# IOIO_Pump_Unrouted.net
KiCad netlist of a schematic drawn in EAGLE
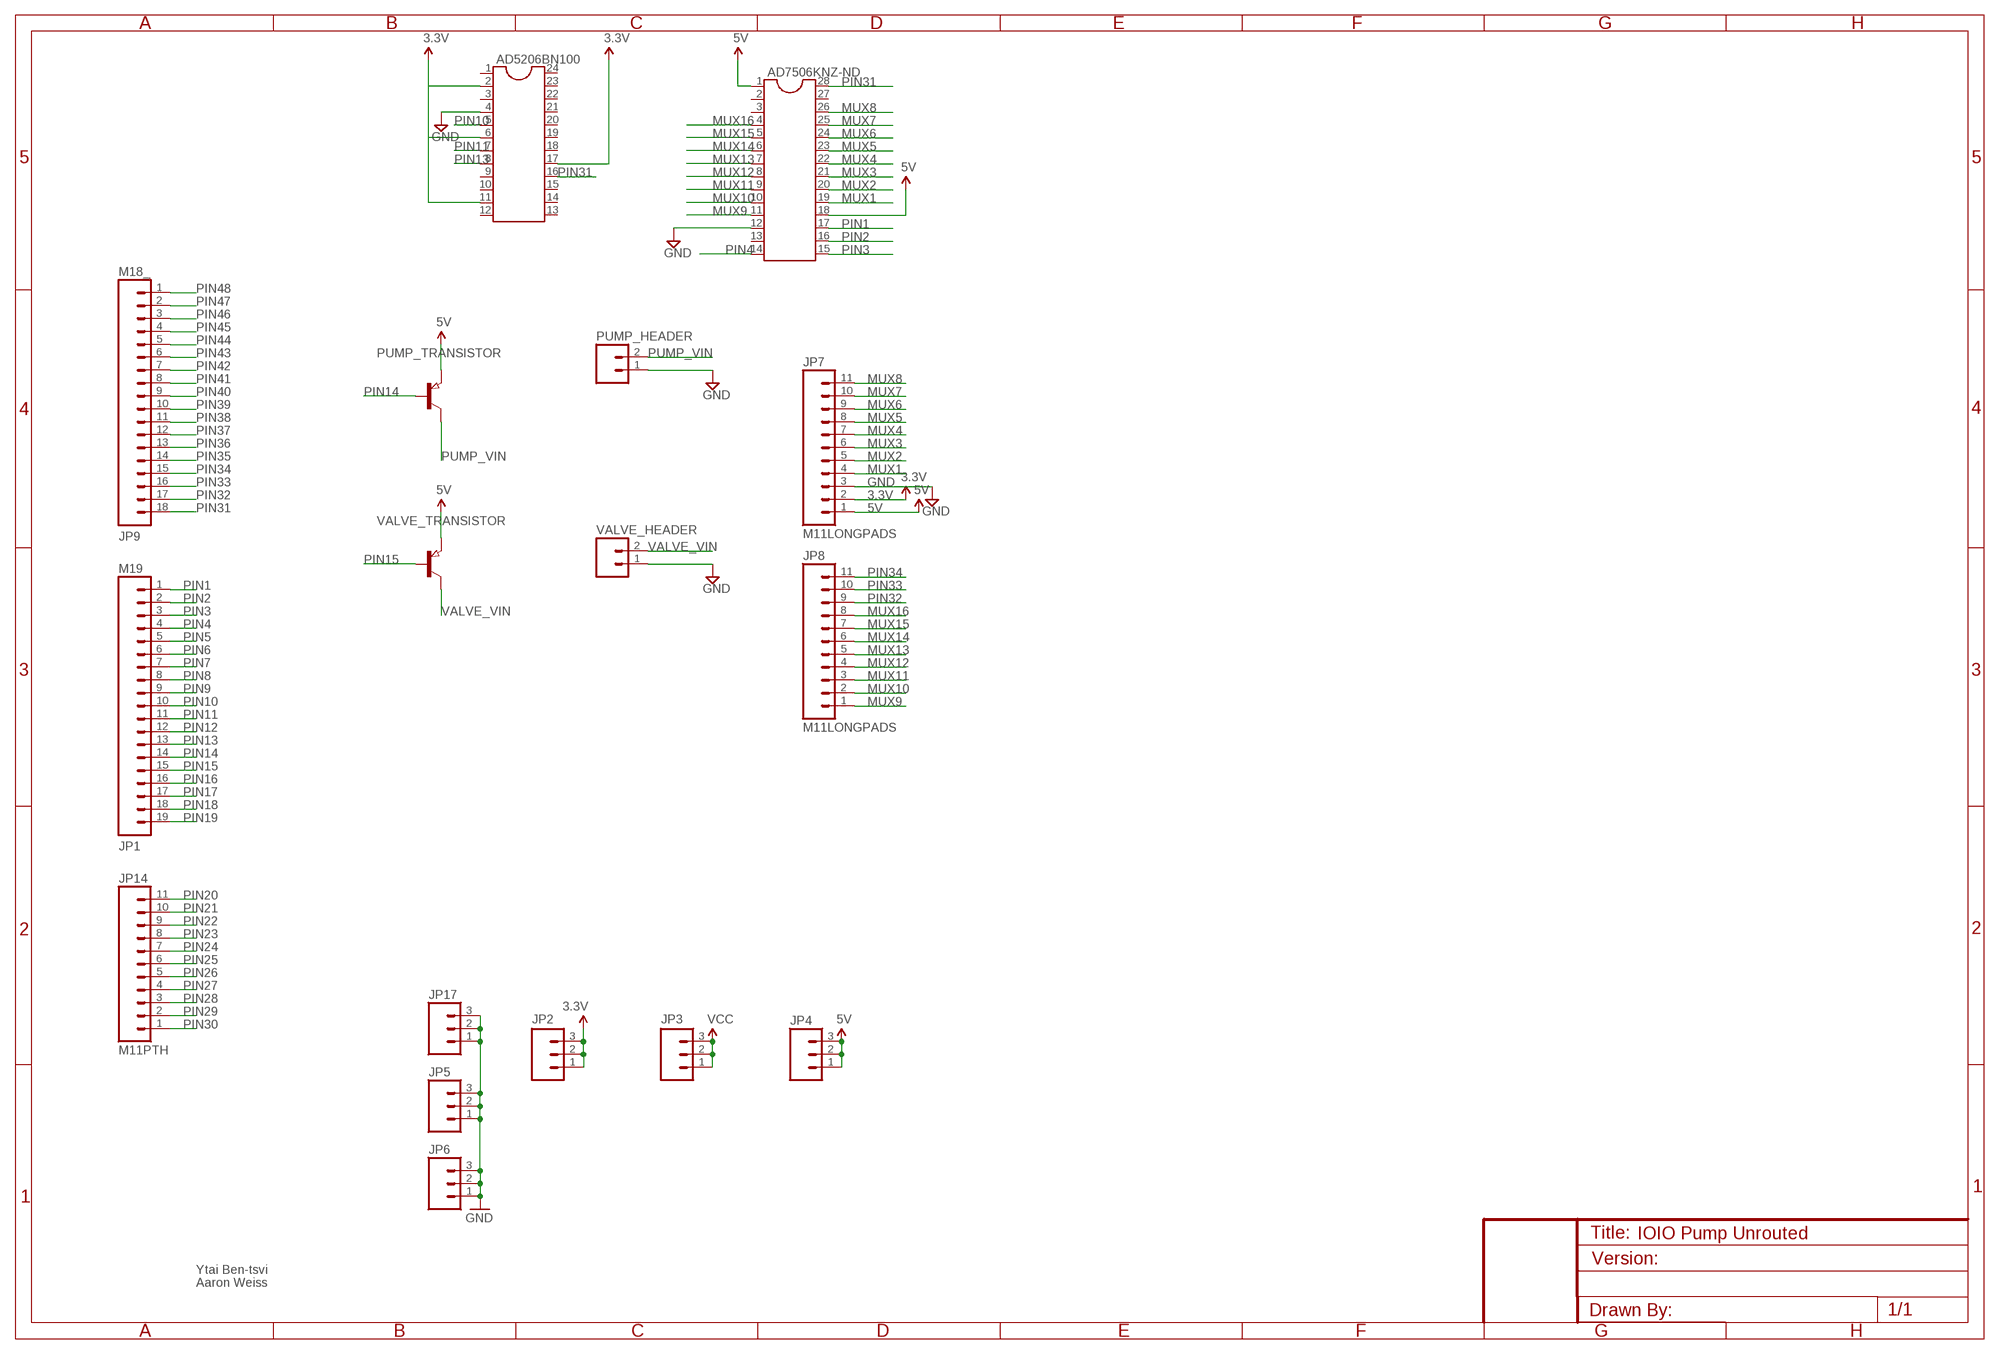
[diagram p0: schematic, sheet 1]

(export (version "E")
  (design (tool "Eeschema 10.0.6"))
  (components
    (comp (ref "AD5206BN100")
      (value "DIL24-3")
      (footprint "eagle-import:DIL24-3")
      (libsource (lib "eagle-import") (part "DIL24-3"))
    )
    (comp (ref "AD7506KNZ-ND")
      (value "DIL28")
      (footprint "eagle-import:DIL28-6")
      (libsource (lib "eagle-import") (part "DIL28"))
    )
    (comp (ref "JP1")
      (value "M19")
      (footprint "eagle-import:1X19")
      (libsource (lib "eagle-import") (part "M19"))
    )
    (comp (ref "JP2")
      (value "M03PTH")
      (footprint "eagle-import:1X03")
      (libsource (lib "eagle-import") (part "M03PTH"))
    )
    (comp (ref "JP3")
      (value "M03PTH")
      (footprint "eagle-import:1X03")
      (libsource (lib "eagle-import") (part "M03PTH"))
    )
    (comp (ref "JP4")
      (value "M03PTH")
      (footprint "eagle-import:1X03")
      (libsource (lib "eagle-import") (part "M03PTH"))
    )
    (comp (ref "JP5")
      (value "M03PTH")
      (footprint "eagle-import:1X03")
      (libsource (lib "eagle-import") (part "M03PTH"))
    )
    (comp (ref "JP6")
      (value "M03PTH")
      (footprint "eagle-import:1X03")
      (libsource (lib "eagle-import") (part "M03PTH"))
    )
    (comp (ref "JP7")
      (value "M11LONGPADS")
      (footprint "eagle-import:1X11_LONGPADS")
      (libsource (lib "eagle-import") (part "M11LONGPADS"))
    )
    (comp (ref "JP8")
      (value "M11LONGPADS")
      (footprint "eagle-import:1X11_LONGPADS")
      (libsource (lib "eagle-import") (part "M11LONGPADS"))
    )
    (comp (ref "JP9")
      (value "M18_")
      (footprint "eagle-import:1X18")
      (libsource (lib "eagle-import") (part "M18_"))
    )
    (comp (ref "JP14")
      (value "M11PTH")
      (footprint "eagle-import:1X11")
      (libsource (lib "eagle-import") (part "M11PTH"))
    )
    (comp (ref "JP17")
      (value "M03PTH")
      (footprint "eagle-import:1X03")
      (libsource (lib "eagle-import") (part "M03PTH"))
    )
    (comp (ref "PUMP_HEADER")
      (value "M02PTH")
      (footprint "eagle-import:1X02")
      (libsource (lib "eagle-import") (part "M02PTH"))
    )
    (comp (ref "PUMP_TRANSISTOR")
      (value "PNP-TRANSISTOR_SOT23")
      (footprint "eagle-import:SOT23")
      (libsource (lib "eagle-import") (part "PNP-TRANSISTOR_SOT23"))
    )
    (comp (ref "VALVE_HEADER")
      (value "M02PTH")
      (footprint "eagle-import:1X02")
      (libsource (lib "eagle-import") (part "M02PTH"))
    )
    (comp (ref "VALVE_TRANSISTOR")
      (value "PNP-TRANSISTOR_SOT23")
      (footprint "eagle-import:SOT23")
      (libsource (lib "eagle-import") (part "PNP-TRANSISTOR_SOT23"))
    )
  )
  (nets
    (net (code "1") (name "/MUX1") (class "Default")
      (node (ref "AD7506KNZ-ND") (pin "19") (pinfunction "19_19") (pintype "passive"))
      (node (ref "JP7") (pin "4") (pinfunction "4_4") (pintype "passive"))
    )
    (net (code "2") (name "/MUX2") (class "Default")
      (node (ref "AD7506KNZ-ND") (pin "20") (pinfunction "20_20") (pintype "passive"))
      (node (ref "JP7") (pin "5") (pinfunction "5_5") (pintype "passive"))
    )
    (net (code "3") (name "/MUX3") (class "Default")
      (node (ref "AD7506KNZ-ND") (pin "21") (pinfunction "21_21") (pintype "passive"))
      (node (ref "JP7") (pin "6") (pinfunction "6_6") (pintype "passive"))
    )
    (net (code "4") (name "/MUX4") (class "Default")
      (node (ref "AD7506KNZ-ND") (pin "22") (pinfunction "22_22") (pintype "passive"))
      (node (ref "JP7") (pin "7") (pinfunction "7_7") (pintype "passive"))
    )
    (net (code "5") (name "/MUX5") (class "Default")
      (node (ref "AD7506KNZ-ND") (pin "23") (pinfunction "23_23") (pintype "passive"))
      (node (ref "JP7") (pin "8") (pinfunction "8_8") (pintype "passive"))
    )
    (net (code "6") (name "/MUX6") (class "Default")
      (node (ref "AD7506KNZ-ND") (pin "24") (pinfunction "24_24") (pintype "passive"))
      (node (ref "JP7") (pin "9") (pinfunction "9_9") (pintype "passive"))
    )
    (net (code "7") (name "/MUX7") (class "Default")
      (node (ref "AD7506KNZ-ND") (pin "25") (pinfunction "25_25") (pintype "passive"))
      (node (ref "JP7") (pin "10") (pinfunction "10_10") (pintype "passive"))
    )
    (net (code "8") (name "/MUX8") (class "Default")
      (node (ref "AD7506KNZ-ND") (pin "26") (pinfunction "26_26") (pintype "passive"))
      (node (ref "JP7") (pin "11") (pinfunction "11_11") (pintype "passive"))
    )
    (net (code "9") (name "/MUX9") (class "Default")
      (node (ref "AD7506KNZ-ND") (pin "11") (pinfunction "11_11") (pintype "passive"))
      (node (ref "JP8") (pin "1") (pinfunction "1_1") (pintype "passive"))
    )
    (net (code "10") (name "/MUX10") (class "Default")
      (node (ref "AD7506KNZ-ND") (pin "10") (pinfunction "10_10") (pintype "passive"))
      (node (ref "JP8") (pin "2") (pinfunction "2_2") (pintype "passive"))
    )
    (net (code "11") (name "/MUX11") (class "Default")
      (node (ref "AD7506KNZ-ND") (pin "9") (pinfunction "9_9") (pintype "passive"))
      (node (ref "JP8") (pin "3") (pinfunction "3_3") (pintype "passive"))
    )
    (net (code "12") (name "/MUX12") (class "Default")
      (node (ref "AD7506KNZ-ND") (pin "8") (pinfunction "8_8") (pintype "passive"))
      (node (ref "JP8") (pin "4") (pinfunction "4_4") (pintype "passive"))
    )
    (net (code "13") (name "/MUX13") (class "Default")
      (node (ref "AD7506KNZ-ND") (pin "7") (pinfunction "7_7") (pintype "passive"))
      (node (ref "JP8") (pin "5") (pinfunction "5_5") (pintype "passive"))
    )
    (net (code "14") (name "/MUX14") (class "Default")
      (node (ref "AD7506KNZ-ND") (pin "6") (pinfunction "6_6") (pintype "passive"))
      (node (ref "JP8") (pin "6") (pinfunction "6_6") (pintype "passive"))
    )
    (net (code "15") (name "/MUX15") (class "Default")
      (node (ref "AD7506KNZ-ND") (pin "5") (pinfunction "5_5") (pintype "passive"))
      (node (ref "JP8") (pin "7") (pinfunction "7_7") (pintype "passive"))
    )
    (net (code "16") (name "/MUX16") (class "Default")
      (node (ref "AD7506KNZ-ND") (pin "4") (pinfunction "4_4") (pintype "passive"))
      (node (ref "JP8") (pin "8") (pinfunction "8_8") (pintype "passive"))
    )
    (net (code "17") (name "/PIN1") (class "Default")
      (node (ref "AD7506KNZ-ND") (pin "17") (pinfunction "17_17") (pintype "passive"))
      (node (ref "JP1") (pin "1") (pinfunction "1_1") (pintype "passive"))
    )
    (net (code "18") (name "/PIN2") (class "Default")
      (node (ref "AD7506KNZ-ND") (pin "16") (pinfunction "16_16") (pintype "passive"))
      (node (ref "JP1") (pin "2") (pinfunction "2_2") (pintype "passive"))
    )
    (net (code "19") (name "/PIN3") (class "Default")
      (node (ref "AD7506KNZ-ND") (pin "15") (pinfunction "15_15") (pintype "passive"))
      (node (ref "JP1") (pin "3") (pinfunction "3_3") (pintype "passive"))
    )
    (net (code "20") (name "/PIN4") (class "Default")
      (node (ref "AD7506KNZ-ND") (pin "14") (pinfunction "14_14") (pintype "passive"))
      (node (ref "JP1") (pin "4") (pinfunction "4_4") (pintype "passive"))
    )
    (net (code "21") (name "/PIN5") (class "Default")
      (node (ref "JP1") (pin "5") (pinfunction "5_5") (pintype "passive"))
    )
    (net (code "22") (name "/PIN6") (class "Default")
      (node (ref "JP1") (pin "6") (pinfunction "6_6") (pintype "passive"))
    )
    (net (code "23") (name "/PIN7") (class "Default")
      (node (ref "JP1") (pin "7") (pinfunction "7_7") (pintype "passive"))
    )
    (net (code "24") (name "/PIN8") (class "Default")
      (node (ref "JP1") (pin "8") (pinfunction "8_8") (pintype "passive"))
    )
    (net (code "25") (name "/PIN9") (class "Default")
      (node (ref "JP1") (pin "9") (pinfunction "9_9") (pintype "passive"))
    )
    (net (code "26") (name "/PIN10") (class "Default")
      (node (ref "AD5206BN100") (pin "5") (pinfunction "5_5") (pintype "passive"))
      (node (ref "JP1") (pin "10") (pinfunction "10_10") (pintype "passive"))
    )
    (net (code "27") (name "/PIN11") (class "Default")
      (node (ref "AD5206BN100") (pin "7") (pinfunction "7_7") (pintype "passive"))
      (node (ref "JP1") (pin "11") (pinfunction "11_11") (pintype "passive"))
    )
    (net (code "28") (name "/PIN12") (class "Default")
      (node (ref "JP1") (pin "12") (pinfunction "12_12") (pintype "passive"))
    )
    (net (code "29") (name "/PIN13") (class "Default")
      (node (ref "AD5206BN100") (pin "8") (pinfunction "8_8") (pintype "passive"))
      (node (ref "JP1") (pin "13") (pinfunction "13_13") (pintype "passive"))
    )
    (net (code "30") (name "/PIN14") (class "Default")
      (node (ref "JP1") (pin "14") (pinfunction "14_14") (pintype "passive"))
      (node (ref "PUMP_TRANSISTOR") (pin "1") (pinfunction "B_1") (pintype "passive"))
    )
    (net (code "31") (name "/PIN15") (class "Default")
      (node (ref "JP1") (pin "15") (pinfunction "15_15") (pintype "passive"))
      (node (ref "VALVE_TRANSISTOR") (pin "1") (pinfunction "B_1") (pintype "passive"))
    )
    (net (code "32") (name "/PIN16") (class "Default")
      (node (ref "JP1") (pin "16") (pinfunction "16_16") (pintype "passive"))
    )
    (net (code "33") (name "/PIN17") (class "Default")
      (node (ref "JP1") (pin "17") (pinfunction "17_17") (pintype "passive"))
    )
    (net (code "34") (name "/PIN18") (class "Default")
      (node (ref "JP1") (pin "18") (pinfunction "18_18") (pintype "passive"))
    )
    (net (code "35") (name "/PIN19") (class "Default")
      (node (ref "JP1") (pin "19") (pinfunction "19_19") (pintype "passive"))
    )
    (net (code "36") (name "/PIN20") (class "Default")
      (node (ref "JP14") (pin "11") (pinfunction "11_11") (pintype "passive"))
    )
    (net (code "37") (name "/PIN21") (class "Default")
      (node (ref "JP14") (pin "10") (pinfunction "10_10") (pintype "passive"))
    )
    (net (code "38") (name "/PIN22") (class "Default")
      (node (ref "JP14") (pin "9") (pinfunction "9_9") (pintype "passive"))
    )
    (net (code "39") (name "/PIN23") (class "Default")
      (node (ref "JP14") (pin "8") (pinfunction "8_8") (pintype "passive"))
    )
    (net (code "40") (name "/PIN24") (class "Default")
      (node (ref "JP14") (pin "7") (pinfunction "7_7") (pintype "passive"))
    )
    (net (code "41") (name "/PIN25") (class "Default")
      (node (ref "JP14") (pin "6") (pinfunction "6_6") (pintype "passive"))
    )
    (net (code "42") (name "/PIN26") (class "Default")
      (node (ref "JP14") (pin "5") (pinfunction "5_5") (pintype "passive"))
    )
    (net (code "43") (name "/PIN27") (class "Default")
      (node (ref "JP14") (pin "4") (pinfunction "4_4") (pintype "passive"))
    )
    (net (code "44") (name "/PIN28") (class "Default")
      (node (ref "JP14") (pin "3") (pinfunction "3_3") (pintype "passive"))
    )
    (net (code "45") (name "/PIN29") (class "Default")
      (node (ref "JP14") (pin "2") (pinfunction "2_2") (pintype "passive"))
    )
    (net (code "46") (name "/PIN30") (class "Default")
      (node (ref "JP14") (pin "1") (pinfunction "1_1") (pintype "passive"))
    )
    (net (code "47") (name "/PIN31") (class "Default")
      (node (ref "AD5206BN100") (pin "16") (pinfunction "16_16") (pintype "passive"))
      (node (ref "AD7506KNZ-ND") (pin "28") (pinfunction "28_28") (pintype "passive"))
      (node (ref "JP9") (pin "18") (pinfunction "18_18") (pintype "passive"))
    )
    (net (code "48") (name "/PIN32") (class "Default")
      (node (ref "JP8") (pin "9") (pinfunction "9_9") (pintype "passive"))
      (node (ref "JP9") (pin "17") (pinfunction "17_17") (pintype "passive"))
    )
    (net (code "49") (name "/PIN33") (class "Default")
      (node (ref "JP8") (pin "10") (pinfunction "10_10") (pintype "passive"))
      (node (ref "JP9") (pin "16") (pinfunction "16_16") (pintype "passive"))
    )
    (net (code "50") (name "/PIN34") (class "Default")
      (node (ref "JP8") (pin "11") (pinfunction "11_11") (pintype "passive"))
      (node (ref "JP9") (pin "15") (pinfunction "15_15") (pintype "passive"))
    )
    (net (code "51") (name "/PIN35") (class "Default")
      (node (ref "JP9") (pin "14") (pinfunction "14_14") (pintype "passive"))
    )
    (net (code "52") (name "/PIN36") (class "Default")
      (node (ref "JP9") (pin "13") (pinfunction "13_13") (pintype "passive"))
    )
    (net (code "53") (name "/PIN37") (class "Default")
      (node (ref "JP9") (pin "12") (pinfunction "12_12") (pintype "passive"))
    )
    (net (code "54") (name "/PIN38") (class "Default")
      (node (ref "JP9") (pin "11") (pinfunction "11_11") (pintype "passive"))
    )
    (net (code "55") (name "/PIN39") (class "Default")
      (node (ref "JP9") (pin "10") (pinfunction "10_10") (pintype "passive"))
    )
    (net (code "56") (name "/PIN40") (class "Default")
      (node (ref "JP9") (pin "9") (pinfunction "9_9") (pintype "passive"))
    )
    (net (code "57") (name "/PIN41") (class "Default")
      (node (ref "JP9") (pin "8") (pinfunction "8_8") (pintype "passive"))
    )
    (net (code "58") (name "/PIN42") (class "Default")
      (node (ref "JP9") (pin "7") (pinfunction "7_7") (pintype "passive"))
    )
    (net (code "59") (name "/PIN43") (class "Default")
      (node (ref "JP9") (pin "6") (pinfunction "6_6") (pintype "passive"))
    )
    (net (code "60") (name "/PIN44") (class "Default")
      (node (ref "JP9") (pin "5") (pinfunction "5_5") (pintype "passive"))
    )
    (net (code "61") (name "/PIN45") (class "Default")
      (node (ref "JP9") (pin "4") (pinfunction "4_4") (pintype "passive"))
    )
    (net (code "62") (name "/PIN46") (class "Default")
      (node (ref "JP9") (pin "3") (pinfunction "3_3") (pintype "passive"))
    )
    (net (code "63") (name "/PIN47") (class "Default")
      (node (ref "JP9") (pin "2") (pinfunction "2_2") (pintype "passive"))
    )
    (net (code "64") (name "/PIN48") (class "Default")
      (node (ref "JP9") (pin "1") (pinfunction "1_1") (pintype "passive"))
    )
    (net (code "65") (name "/PUMP_VIN") (class "Default")
      (node (ref "PUMP_HEADER") (pin "2") (pinfunction "2_2") (pintype "passive"))
      (node (ref "PUMP_TRANSISTOR") (pin "3") (pinfunction "C_3") (pintype "passive"))
    )
    (net (code "66") (name "/VALVE_VIN") (class "Default")
      (node (ref "VALVE_HEADER") (pin "2") (pinfunction "2_2") (pintype "passive"))
      (node (ref "VALVE_TRANSISTOR") (pin "3") (pinfunction "C_3") (pintype "passive"))
    )
    (net (code "67") (name "3.3V") (class "Default")
      (node (ref "AD5206BN100") (pin "11") (pinfunction "11_11") (pintype "passive"))
      (node (ref "AD5206BN100") (pin "17") (pinfunction "17_17") (pintype "passive"))
      (node (ref "AD5206BN100") (pin "2") (pinfunction "2_2") (pintype "passive"))
      (node (ref "AD5206BN100") (pin "6") (pinfunction "6_6") (pintype "passive"))
      (node (ref "JP2") (pin "1") (pinfunction "1_1") (pintype "passive"))
      (node (ref "JP2") (pin "2") (pinfunction "2_2") (pintype "passive"))
      (node (ref "JP2") (pin "3") (pinfunction "3_3") (pintype "passive"))
      (node (ref "JP7") (pin "2") (pinfunction "2_2") (pintype "passive"))
    )
    (net (code "68") (name "5V") (class "Default")
      (node (ref "AD7506KNZ-ND") (pin "1") (pinfunction "1_1") (pintype "passive"))
      (node (ref "AD7506KNZ-ND") (pin "18") (pinfunction "18_18") (pintype "passive"))
      (node (ref "JP4") (pin "1") (pinfunction "1_1") (pintype "passive"))
      (node (ref "JP4") (pin "2") (pinfunction "2_2") (pintype "passive"))
      (node (ref "JP4") (pin "3") (pinfunction "3_3") (pintype "passive"))
      (node (ref "JP7") (pin "1") (pinfunction "1_1") (pintype "passive"))
      (node (ref "PUMP_TRANSISTOR") (pin "2") (pinfunction "E_2") (pintype "passive"))
      (node (ref "VALVE_TRANSISTOR") (pin "2") (pinfunction "E_2") (pintype "passive"))
    )
    (net (code "69") (name "GND") (class "Default")
      (node (ref "AD5206BN100") (pin "4") (pinfunction "4_4") (pintype "passive"))
      (node (ref "AD7506KNZ-ND") (pin "12") (pinfunction "12_12") (pintype "passive"))
      (node (ref "JP17") (pin "1") (pinfunction "1_1") (pintype "passive"))
      (node (ref "JP17") (pin "2") (pinfunction "2_2") (pintype "passive"))
      (node (ref "JP17") (pin "3") (pinfunction "3_3") (pintype "passive"))
      (node (ref "JP5") (pin "1") (pinfunction "1_1") (pintype "passive"))
      (node (ref "JP5") (pin "2") (pinfunction "2_2") (pintype "passive"))
      (node (ref "JP5") (pin "3") (pinfunction "3_3") (pintype "passive"))
      (node (ref "JP6") (pin "1") (pinfunction "1_1") (pintype "passive"))
      (node (ref "JP6") (pin "2") (pinfunction "2_2") (pintype "passive"))
      (node (ref "JP6") (pin "3") (pinfunction "3_3") (pintype "passive"))
      (node (ref "JP7") (pin "3") (pinfunction "3_3") (pintype "passive"))
      (node (ref "PUMP_HEADER") (pin "1") (pinfunction "1_1") (pintype "passive"))
      (node (ref "VALVE_HEADER") (pin "1") (pinfunction "1_1") (pintype "passive"))
    )
    (net (code "70") (name "VCC") (class "Default")
      (node (ref "JP3") (pin "1") (pinfunction "1_1") (pintype "passive"))
      (node (ref "JP3") (pin "2") (pinfunction "2_2") (pintype "passive"))
      (node (ref "JP3") (pin "3") (pinfunction "3_3") (pintype "passive"))
    )
    (net (code "71") (name "unconnected-(AD5206BN100-Pad1)") (class "Default")
      (node (ref "AD5206BN100") (pin "1") (pinfunction "1_1") (pintype "passive"))
    )
    (net (code "72") (name "unconnected-(AD5206BN100-Pad3)") (class "Default")
      (node (ref "AD5206BN100") (pin "3") (pinfunction "3_3") (pintype "passive"))
    )
    (net (code "73") (name "unconnected-(AD5206BN100-Pad9)") (class "Default")
      (node (ref "AD5206BN100") (pin "9") (pinfunction "9_9") (pintype "passive"))
    )
    (net (code "74") (name "unconnected-(AD5206BN100-Pad10)") (class "Default")
      (node (ref "AD5206BN100") (pin "10") (pinfunction "10_10") (pintype "passive"))
    )
    (net (code "75") (name "unconnected-(AD5206BN100-Pad12)") (class "Default")
      (node (ref "AD5206BN100") (pin "12") (pinfunction "12_12") (pintype "passive"))
    )
    (net (code "76") (name "unconnected-(AD5206BN100-Pad13)") (class "Default")
      (node (ref "AD5206BN100") (pin "13") (pinfunction "13_13") (pintype "passive"))
    )
    (net (code "77") (name "unconnected-(AD5206BN100-Pad14)") (class "Default")
      (node (ref "AD5206BN100") (pin "14") (pinfunction "14_14") (pintype "passive"))
    )
    (net (code "78") (name "unconnected-(AD5206BN100-Pad15)") (class "Default")
      (node (ref "AD5206BN100") (pin "15") (pinfunction "15_15") (pintype "passive"))
    )
    (net (code "79") (name "unconnected-(AD5206BN100-Pad18)") (class "Default")
      (node (ref "AD5206BN100") (pin "18") (pinfunction "18_18") (pintype "passive"))
    )
    (net (code "80") (name "unconnected-(AD5206BN100-Pad19)") (class "Default")
      (node (ref "AD5206BN100") (pin "19") (pinfunction "19_19") (pintype "passive"))
    )
    (net (code "81") (name "unconnected-(AD5206BN100-Pad20)") (class "Default")
      (node (ref "AD5206BN100") (pin "20") (pinfunction "20_20") (pintype "passive"))
    )
    (net (code "82") (name "unconnected-(AD5206BN100-Pad21)") (class "Default")
      (node (ref "AD5206BN100") (pin "21") (pinfunction "21_21") (pintype "passive"))
    )
    (net (code "83") (name "unconnected-(AD5206BN100-Pad22)") (class "Default")
      (node (ref "AD5206BN100") (pin "22") (pinfunction "22_22") (pintype "passive"))
    )
    (net (code "84") (name "unconnected-(AD5206BN100-Pad23)") (class "Default")
      (node (ref "AD5206BN100") (pin "23") (pinfunction "23_23") (pintype "passive"))
    )
    (net (code "85") (name "unconnected-(AD5206BN100-Pad24)") (class "Default")
      (node (ref "AD5206BN100") (pin "24") (pinfunction "24_24") (pintype "passive"))
    )
    (net (code "86") (name "unconnected-(AD7506KNZ-ND-Pad2)") (class "Default")
      (node (ref "AD7506KNZ-ND") (pin "2") (pinfunction "2_2") (pintype "passive"))
    )
    (net (code "87") (name "unconnected-(AD7506KNZ-ND-Pad3)") (class "Default")
      (node (ref "AD7506KNZ-ND") (pin "3") (pinfunction "3_3") (pintype "passive"))
    )
    (net (code "88") (name "unconnected-(AD7506KNZ-ND-Pad13)") (class "Default")
      (node (ref "AD7506KNZ-ND") (pin "13") (pinfunction "13_13") (pintype "passive"))
    )
    (net (code "89") (name "unconnected-(AD7506KNZ-ND-Pad27)") (class "Default")
      (node (ref "AD7506KNZ-ND") (pin "27") (pinfunction "27_27") (pintype "passive"))
    )
  )
)
